# TSAL.net
KiCad netlist of a schematic drawn in Altium Designer
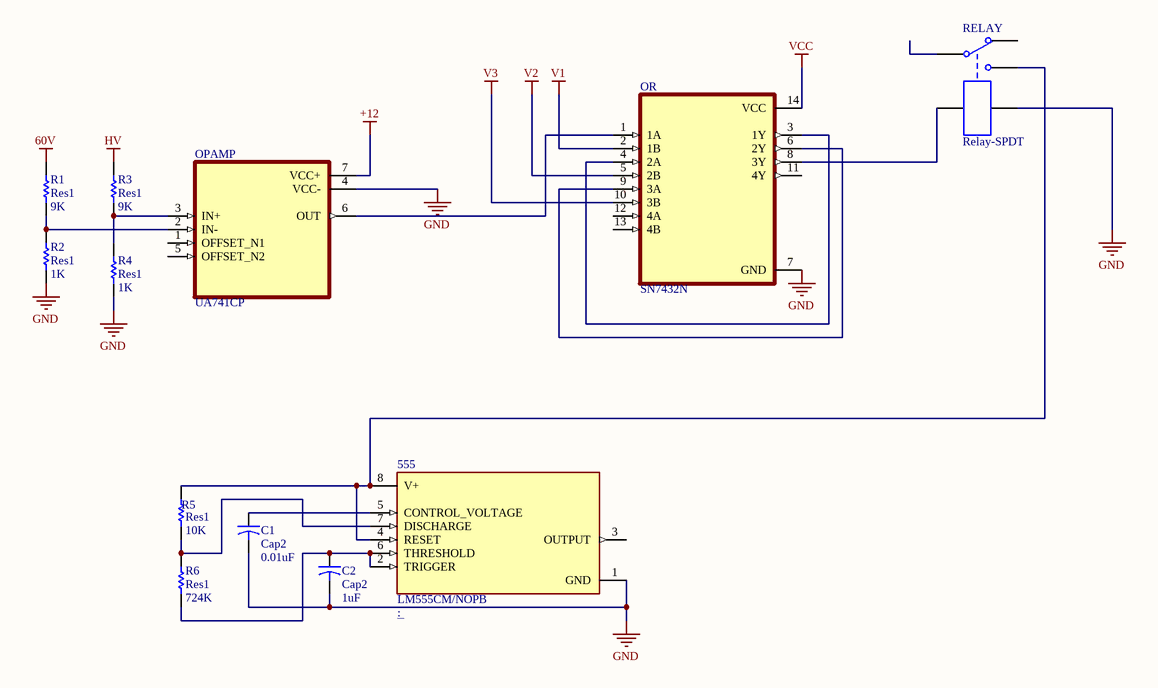
[diagram p0: TSAL.SchDoc]

(export (version "E")
  (design (tool "Eeschema 10.0.6"))
  (components
    (comp (ref "555")
      (value "LM555CM/NOPB")
      (footprint "SOIC127P599X175-8N")
      (description "Highly Stable 555 Timer 8-SOIC 0 to 70")
      (fields (field (name "MF") "Texas Instruments"))
      (libsource (lib "LM555CM_NOPB") (part "LM555CM/NOPB"))
    )
    (comp (ref "C1")
      (value "Cap2")
      (footprint "CAPR5-4X5")
      (description "Capacitor")
      (fields (field (name "ALTIUM_VALUE") "0.01uF") (field (name "PUBLISHER") "Altium Limited"))
      (libsource (lib "Miscellaneous Devices") (part "Cap2"))
    )
    (comp (ref "C2")
      (value "Cap2")
      (footprint "CAPR5-4X5")
      (description "Capacitor")
      (fields (field (name "ALTIUM_VALUE") "1uF") (field (name "PUBLISHER") "Altium Limited"))
      (libsource (lib "Miscellaneous Devices") (part "Cap2"))
    )
    (comp (ref "OPAMP")
      (value "UA741CP")
      (footprint "DIP794W45P254L959H508Q8")
      (description "General-Purpose Operational Amplifier")
      (fields (field (name "MF") "Texas Instruments"))
      (libsource (lib "UA741CP") (part "UA741CP"))
    )
    (comp (ref "OR")
      (value "SN7432N")
      (footprint "DIP794W45P254L1969H508Q14")
      (description "Quad 2-input positive-OR gates 14-PDIP 0 to 70")
      (fields (field (name "MF") "Texas Instruments"))
      (libsource (lib "SN7432N") (part "SN7432N"))
    )
    (comp (ref "R1")
      (value "Res1")
      (footprint "AXIAL-0.3")
      (description "Resistor")
      (fields (field (name "ALTIUM_VALUE") "9K") (field (name "PUBLISHER") "Altium Limited"))
      (libsource (lib "Miscellaneous Devices") (part "Res1"))
    )
    (comp (ref "R2")
      (value "Res1")
      (footprint "AXIAL-0.3")
      (description "Resistor")
      (fields (field (name "ALTIUM_VALUE") "1K") (field (name "PUBLISHER") "Altium Limited"))
      (libsource (lib "Miscellaneous Devices") (part "Res1"))
    )
    (comp (ref "R3")
      (value "Res1")
      (footprint "AXIAL-0.3")
      (description "Resistor")
      (fields (field (name "ALTIUM_VALUE") "9K") (field (name "PUBLISHER") "Altium Limited"))
      (libsource (lib "Miscellaneous Devices") (part "Res1"))
    )
    (comp (ref "R4")
      (value "Res1")
      (footprint "AXIAL-0.3")
      (description "Resistor")
      (fields (field (name "ALTIUM_VALUE") "1K") (field (name "PUBLISHER") "Altium Limited"))
      (libsource (lib "Miscellaneous Devices") (part "Res1"))
    )
    (comp (ref "R5")
      (value "Res1")
      (footprint "AXIAL-0.3")
      (description "Resistor")
      (fields (field (name "ALTIUM_VALUE") "10K") (field (name "PUBLISHER") "Altium Limited"))
      (libsource (lib "Miscellaneous Devices") (part "Res1"))
    )
    (comp (ref "R6")
      (value "Res1")
      (footprint "AXIAL-0.3")
      (description "Resistor")
      (fields (field (name "ALTIUM_VALUE") "724K") (field (name "PUBLISHER") "Altium Limited"))
      (libsource (lib "Miscellaneous Devices") (part "Res1"))
    )
    (comp (ref "RELAY")
      (value "Relay-SPDT")
      (footprint "MODULE5B")
      (description "Single-Pole Dual-Throw Relay")
      (fields (field (name "PUBLISHER") "Altium Limited"))
      (libsource (lib "Miscellaneous Devices") (part "Relay-SPDT"))
    )
  )
  (nets
    (net (code "1") (name "+12") (class "Default")
      (node (ref "OPAMP") (pin "7") (pinfunction "VCC+_7") (pintype "power_in"))
    )
    (net (code "2") (name "60V") (class "Default")
      (node (ref "R1") (pin "1") (pinfunction "1_1") (pintype "passive"))
    )
    (net (code "3") (name "GND") (class "Default")
      (node (ref "555") (pin "1") (pinfunction "GND_1") (pintype "power_in"))
      (node (ref "C1") (pin "2") (pinfunction "2_2") (pintype "passive"))
      (node (ref "C2") (pin "2") (pinfunction "2_2") (pintype "passive"))
      (node (ref "OPAMP") (pin "4") (pinfunction "VCC-_4") (pintype "power_in"))
      (node (ref "OR") (pin "7") (pinfunction "GND_7") (pintype "power_in"))
      (node (ref "R2") (pin "2") (pinfunction "2_2") (pintype "passive"))
      (node (ref "R4") (pin "2") (pinfunction "2_2") (pintype "passive"))
      (node (ref "RELAY") (pin "5") (pinfunction "5_5") (pintype "passive"))
    )
    (net (code "4") (name "HV") (class "Default")
      (node (ref "R3") (pin "1") (pinfunction "1_1") (pintype "passive"))
    )
    (net (code "5") (name "Net-(555-CONTROL_VOLTAGE)") (class "Default")
      (node (ref "555") (pin "5") (pinfunction "CONTROL_VOLTAGE_5") (pintype "input"))
      (node (ref "C1") (pin "1") (pinfunction "1_1") (pintype "passive"))
    )
    (net (code "6") (name "Net-(555-DISCHARGE)") (class "Default")
      (node (ref "555") (pin "7") (pinfunction "DISCHARGE_7") (pintype "input"))
      (node (ref "R5") (pin "2") (pinfunction "2_2") (pintype "passive"))
      (node (ref "R6") (pin "1") (pinfunction "1_1") (pintype "passive"))
    )
    (net (code "7") (name "Net-(555-RESET)") (class "Default")
      (node (ref "555") (pin "4") (pinfunction "RESET_4") (pintype "input"))
      (node (ref "555") (pin "8") (pinfunction "V+_8") (pintype "power_in"))
      (node (ref "R5") (pin "1") (pinfunction "1_1") (pintype "passive"))
      (node (ref "RELAY") (pin "3") (pinfunction "3_3") (pintype "passive"))
    )
    (net (code "8") (name "Net-(555-THRESHOLD)") (class "Default")
      (node (ref "555") (pin "2") (pinfunction "TRIGGER_2") (pintype "input"))
      (node (ref "555") (pin "6") (pinfunction "THRESHOLD_6") (pintype "input"))
      (node (ref "C2") (pin "1") (pinfunction "1_1") (pintype "passive"))
      (node (ref "R6") (pin "2") (pinfunction "2_2") (pintype "passive"))
    )
    (net (code "9") (name "Net-(OPAMP-IN+)") (class "Default")
      (node (ref "OPAMP") (pin "3") (pinfunction "IN+_3") (pintype "input"))
      (node (ref "R3") (pin "2") (pinfunction "2_2") (pintype "passive"))
      (node (ref "R4") (pin "1") (pinfunction "1_1") (pintype "passive"))
    )
    (net (code "10") (name "Net-(OPAMP-IN-)") (class "Default")
      (node (ref "OPAMP") (pin "2") (pinfunction "IN-_2") (pintype "input"))
      (node (ref "R1") (pin "2") (pinfunction "2_2") (pintype "passive"))
      (node (ref "R2") (pin "1") (pinfunction "1_1") (pintype "passive"))
    )
    (net (code "11") (name "Net-(OPAMP-OUT)") (class "Default")
      (node (ref "OPAMP") (pin "6") (pinfunction "OUT_6") (pintype "output"))
      (node (ref "OR") (pin "1") (pinfunction "1A_1") (pintype "input"))
    )
    (net (code "12") (name "Net-(OR-1Y)") (class "Default")
      (node (ref "OR") (pin "3") (pinfunction "1Y_3") (pintype "output"))
      (node (ref "OR") (pin "4") (pinfunction "2A_4") (pintype "input"))
    )
    (net (code "13") (name "Net-(OR-2Y)") (class "Default")
      (node (ref "OR") (pin "6") (pinfunction "2Y_6") (pintype "output"))
      (node (ref "OR") (pin "9") (pinfunction "3A_9") (pintype "input"))
    )
    (net (code "14") (name "Net-(OR-3Y)") (class "Default")
      (node (ref "OR") (pin "8") (pinfunction "3Y_8") (pintype "output"))
      (node (ref "RELAY") (pin "4") (pinfunction "4_4") (pintype "passive"))
    )
    (net (code "15") (name "V1") (class "Default")
      (node (ref "OR") (pin "2") (pinfunction "1B_2") (pintype "input"))
    )
    (net (code "16") (name "V2") (class "Default")
      (node (ref "OR") (pin "5") (pinfunction "2B_5") (pintype "input"))
    )
    (net (code "17") (name "V3") (class "Default")
      (node (ref "OR") (pin "10") (pinfunction "3B_10") (pintype "input"))
    )
    (net (code "18") (name "VCC") (class "Default")
      (node (ref "OR") (pin "14") (pinfunction "VCC_14") (pintype "power_in"))
    )
    (net (code "19") (name "unconnected-(555-OUTPUT-Pad3)") (class "Default")
      (node (ref "555") (pin "3") (pinfunction "OUTPUT_3") (pintype "output"))
    )
    (net (code "20") (name "unconnected-(OPAMP-OFFSET_N1-Pad1)") (class "Default")
      (node (ref "OPAMP") (pin "1") (pinfunction "OFFSET_N1_1") (pintype "input"))
    )
    (net (code "21") (name "unconnected-(OPAMP-OFFSET_N2-Pad5)") (class "Default")
      (node (ref "OPAMP") (pin "5") (pinfunction "OFFSET_N2_5") (pintype "input"))
    )
    (net (code "22") (name "unconnected-(OR-4A-Pad12)") (class "Default")
      (node (ref "OR") (pin "12") (pinfunction "4A_12") (pintype "input"))
    )
    (net (code "23") (name "unconnected-(OR-4B-Pad13)") (class "Default")
      (node (ref "OR") (pin "13") (pinfunction "4B_13") (pintype "input"))
    )
    (net (code "24") (name "unconnected-(OR-4Y-Pad11)") (class "Default")
      (node (ref "OR") (pin "11") (pinfunction "4Y_11") (pintype "output"))
    )
    (net (code "25") (name "unconnected-(RELAY-Pad1)") (class "Default")
      (node (ref "RELAY") (pin "1") (pinfunction "1_1") (pintype "passive"))
    )
    (net (code "26") (name "unconnected-(RELAY-Pad2)") (class "Default")
      (node (ref "RELAY") (pin "2") (pinfunction "2_2") (pintype "passive"))
    )
  )
)
